# Nappe2_0___V2.net
KiCad netlist of a schematic drawn in EAGLE
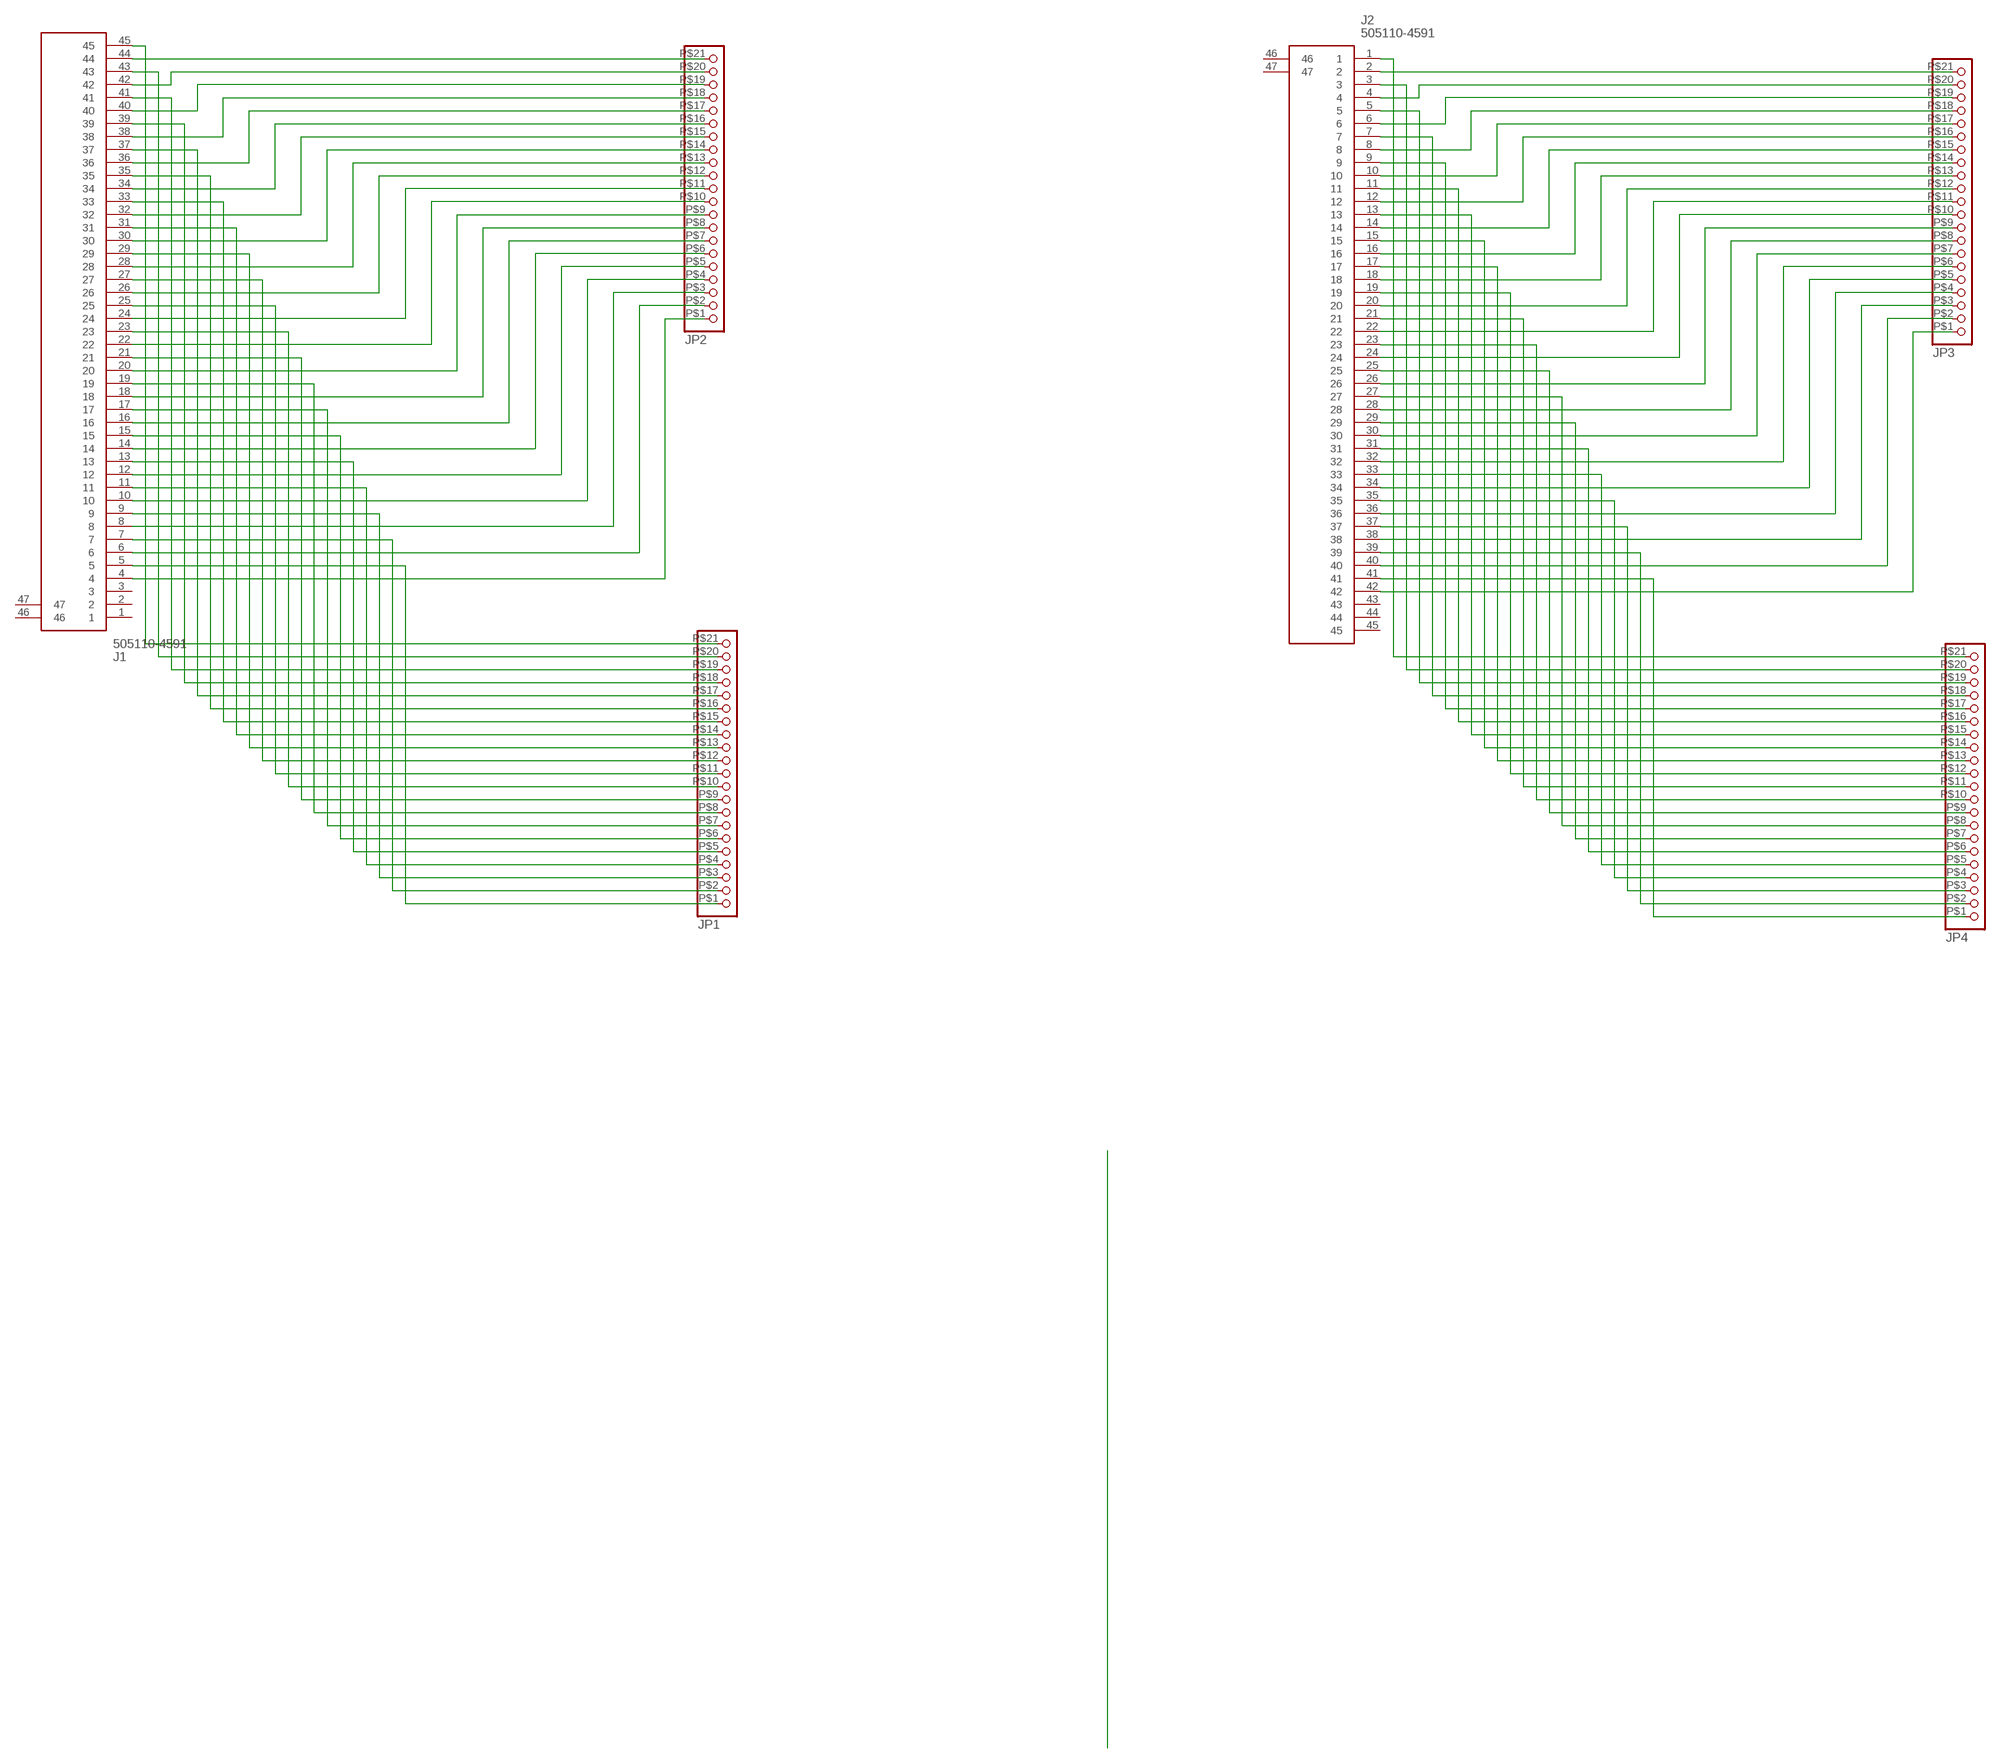
[diagram p0: schematic, sheet 1]

(export (version "E")
  (design (tool "Eeschema 10.0.6"))
  (components
    (comp (ref "J1")
      (value "505110-4591")
      (footprint "eagle-import:5051104591")
      (fields (field (name "MOUSER_PART_NUMBER") "538-505110-4591"))
      (libsource (lib "eagle-import") (part "505110-4591"))
    )
    (comp (ref "J2")
      (value "505110-4591")
      (footprint "eagle-import:5051104591")
      (fields (field (name "MOUSER_PART_NUMBER") "538-505110-4591"))
      (libsource (lib "eagle-import") (part "505110-4591"))
    )
    (comp (ref "JP1")
      (value "PINHD-1X21(2.5)")
      (footprint "eagle-import:1X21(2.5)")
      (libsource (lib "eagle-import") (part "PINHD-1X21(2.5)"))
    )
    (comp (ref "JP2")
      (value "PINHD-1X21(2.5)")
      (footprint "eagle-import:1X21(2.5)")
      (libsource (lib "eagle-import") (part "PINHD-1X21(2.5)"))
    )
    (comp (ref "JP3")
      (value "PINHD-1X21(2.5)")
      (footprint "eagle-import:1X21(2.5)")
      (libsource (lib "eagle-import") (part "PINHD-1X21(2.5)"))
    )
    (comp (ref "JP4")
      (value "PINHD-1X21(2.5)")
      (footprint "eagle-import:1X21(2.5)")
      (libsource (lib "eagle-import") (part "PINHD-1X21(2.5)"))
    )
  )
  (nets
    (net (code "1") (name "Net-(JP1-1)") (class "Default")
      (node (ref "J1") (pin "5") (pinfunction "5_5") (pintype "bidirectional"))
      (node (ref "JP1") (pin "P$1") (pinfunction "1_P$1") (pintype "passive"))
    )
    (net (code "2") (name "Net-(JP1-2)") (class "Default")
      (node (ref "J1") (pin "7") (pinfunction "7_7") (pintype "bidirectional"))
      (node (ref "JP1") (pin "P$2") (pinfunction "2_P$2") (pintype "passive"))
    )
    (net (code "3") (name "Net-(JP1-3)") (class "Default")
      (node (ref "J1") (pin "9") (pinfunction "9_9") (pintype "bidirectional"))
      (node (ref "JP1") (pin "P$3") (pinfunction "3_P$3") (pintype "passive"))
    )
    (net (code "4") (name "Net-(JP1-4)") (class "Default")
      (node (ref "J1") (pin "11") (pinfunction "11_11") (pintype "bidirectional"))
      (node (ref "JP1") (pin "P$4") (pinfunction "4_P$4") (pintype "passive"))
    )
    (net (code "5") (name "Net-(JP1-5)") (class "Default")
      (node (ref "J1") (pin "13") (pinfunction "13_13") (pintype "bidirectional"))
      (node (ref "JP1") (pin "P$5") (pinfunction "5_P$5") (pintype "passive"))
    )
    (net (code "6") (name "Net-(JP1-6)") (class "Default")
      (node (ref "J1") (pin "15") (pinfunction "15_15") (pintype "bidirectional"))
      (node (ref "JP1") (pin "P$6") (pinfunction "6_P$6") (pintype "passive"))
    )
    (net (code "7") (name "Net-(JP1-7)") (class "Default")
      (node (ref "J1") (pin "17") (pinfunction "17_17") (pintype "bidirectional"))
      (node (ref "JP1") (pin "P$7") (pinfunction "7_P$7") (pintype "passive"))
    )
    (net (code "8") (name "Net-(JP1-8)") (class "Default")
      (node (ref "J1") (pin "19") (pinfunction "19_19") (pintype "bidirectional"))
      (node (ref "JP1") (pin "P$8") (pinfunction "8_P$8") (pintype "passive"))
    )
    (net (code "9") (name "Net-(JP1-9)") (class "Default")
      (node (ref "J1") (pin "21") (pinfunction "21_21") (pintype "bidirectional"))
      (node (ref "JP1") (pin "P$9") (pinfunction "9_P$9") (pintype "passive"))
    )
    (net (code "10") (name "Net-(JP1-10)") (class "Default")
      (node (ref "J1") (pin "23") (pinfunction "23_23") (pintype "bidirectional"))
      (node (ref "JP1") (pin "P$10") (pinfunction "10_P$10") (pintype "passive"))
    )
    (net (code "11") (name "Net-(JP1-11)") (class "Default")
      (node (ref "J1") (pin "25") (pinfunction "25_25") (pintype "bidirectional"))
      (node (ref "JP1") (pin "P$11") (pinfunction "11_P$11") (pintype "passive"))
    )
    (net (code "12") (name "Net-(JP1-12)") (class "Default")
      (node (ref "J1") (pin "27") (pinfunction "27_27") (pintype "bidirectional"))
      (node (ref "JP1") (pin "P$12") (pinfunction "12_P$12") (pintype "passive"))
    )
    (net (code "13") (name "Net-(JP1-13)") (class "Default")
      (node (ref "J1") (pin "29") (pinfunction "29_29") (pintype "bidirectional"))
      (node (ref "JP1") (pin "P$13") (pinfunction "13_P$13") (pintype "passive"))
    )
    (net (code "14") (name "Net-(JP1-14)") (class "Default")
      (node (ref "J1") (pin "31") (pinfunction "31_31") (pintype "bidirectional"))
      (node (ref "JP1") (pin "P$14") (pinfunction "14_P$14") (pintype "passive"))
    )
    (net (code "15") (name "Net-(JP1-15)") (class "Default")
      (node (ref "J1") (pin "33") (pinfunction "33_33") (pintype "bidirectional"))
      (node (ref "JP1") (pin "P$15") (pinfunction "15_P$15") (pintype "passive"))
    )
    (net (code "16") (name "Net-(JP1-16)") (class "Default")
      (node (ref "J1") (pin "35") (pinfunction "35_35") (pintype "bidirectional"))
      (node (ref "JP1") (pin "P$16") (pinfunction "16_P$16") (pintype "passive"))
    )
    (net (code "17") (name "Net-(JP1-17)") (class "Default")
      (node (ref "J1") (pin "37") (pinfunction "37_37") (pintype "bidirectional"))
      (node (ref "JP1") (pin "P$17") (pinfunction "17_P$17") (pintype "passive"))
    )
    (net (code "18") (name "Net-(JP1-18)") (class "Default")
      (node (ref "J1") (pin "39") (pinfunction "39_39") (pintype "bidirectional"))
      (node (ref "JP1") (pin "P$18") (pinfunction "18_P$18") (pintype "passive"))
    )
    (net (code "19") (name "Net-(JP1-19)") (class "Default")
      (node (ref "J1") (pin "41") (pinfunction "41_41") (pintype "bidirectional"))
      (node (ref "JP1") (pin "P$19") (pinfunction "19_P$19") (pintype "passive"))
    )
    (net (code "20") (name "Net-(JP1-20)") (class "Default")
      (node (ref "J1") (pin "43") (pinfunction "43_43") (pintype "bidirectional"))
      (node (ref "JP1") (pin "P$20") (pinfunction "20_P$20") (pintype "passive"))
    )
    (net (code "21") (name "Net-(JP1-21)") (class "Default")
      (node (ref "J1") (pin "45") (pinfunction "45_45") (pintype "bidirectional"))
      (node (ref "JP1") (pin "P$21") (pinfunction "21_P$21") (pintype "passive"))
    )
    (net (code "22") (name "Net-(JP2-1)") (class "Default")
      (node (ref "J1") (pin "4") (pinfunction "4_4") (pintype "bidirectional"))
      (node (ref "JP2") (pin "P$1") (pinfunction "1_P$1") (pintype "passive"))
    )
    (net (code "23") (name "Net-(JP2-2)") (class "Default")
      (node (ref "J1") (pin "6") (pinfunction "6_6") (pintype "bidirectional"))
      (node (ref "JP2") (pin "P$2") (pinfunction "2_P$2") (pintype "passive"))
    )
    (net (code "24") (name "Net-(JP2-3)") (class "Default")
      (node (ref "J1") (pin "8") (pinfunction "8_8") (pintype "bidirectional"))
      (node (ref "JP2") (pin "P$3") (pinfunction "3_P$3") (pintype "passive"))
    )
    (net (code "25") (name "Net-(JP2-4)") (class "Default")
      (node (ref "J1") (pin "10") (pinfunction "10_10") (pintype "bidirectional"))
      (node (ref "JP2") (pin "P$4") (pinfunction "4_P$4") (pintype "passive"))
    )
    (net (code "26") (name "Net-(JP2-5)") (class "Default")
      (node (ref "J1") (pin "12") (pinfunction "12_12") (pintype "bidirectional"))
      (node (ref "JP2") (pin "P$5") (pinfunction "5_P$5") (pintype "passive"))
    )
    (net (code "27") (name "Net-(JP2-6)") (class "Default")
      (node (ref "J1") (pin "14") (pinfunction "14_14") (pintype "bidirectional"))
      (node (ref "JP2") (pin "P$6") (pinfunction "6_P$6") (pintype "passive"))
    )
    (net (code "28") (name "Net-(JP2-7)") (class "Default")
      (node (ref "J1") (pin "16") (pinfunction "16_16") (pintype "bidirectional"))
      (node (ref "JP2") (pin "P$7") (pinfunction "7_P$7") (pintype "passive"))
    )
    (net (code "29") (name "Net-(JP2-8)") (class "Default")
      (node (ref "J1") (pin "18") (pinfunction "18_18") (pintype "bidirectional"))
      (node (ref "JP2") (pin "P$8") (pinfunction "8_P$8") (pintype "passive"))
    )
    (net (code "30") (name "Net-(JP2-9)") (class "Default")
      (node (ref "J1") (pin "20") (pinfunction "20_20") (pintype "bidirectional"))
      (node (ref "JP2") (pin "P$9") (pinfunction "9_P$9") (pintype "passive"))
    )
    (net (code "31") (name "Net-(JP2-10)") (class "Default")
      (node (ref "J1") (pin "22") (pinfunction "22_22") (pintype "bidirectional"))
      (node (ref "JP2") (pin "P$10") (pinfunction "10_P$10") (pintype "passive"))
    )
    (net (code "32") (name "Net-(JP2-11)") (class "Default")
      (node (ref "J1") (pin "24") (pinfunction "24_24") (pintype "bidirectional"))
      (node (ref "JP2") (pin "P$11") (pinfunction "11_P$11") (pintype "passive"))
    )
    (net (code "33") (name "Net-(JP2-12)") (class "Default")
      (node (ref "J1") (pin "26") (pinfunction "26_26") (pintype "bidirectional"))
      (node (ref "JP2") (pin "P$12") (pinfunction "12_P$12") (pintype "passive"))
    )
    (net (code "34") (name "Net-(JP2-13)") (class "Default")
      (node (ref "J1") (pin "28") (pinfunction "28_28") (pintype "bidirectional"))
      (node (ref "JP2") (pin "P$13") (pinfunction "13_P$13") (pintype "passive"))
    )
    (net (code "35") (name "Net-(JP2-14)") (class "Default")
      (node (ref "J1") (pin "30") (pinfunction "30_30") (pintype "bidirectional"))
      (node (ref "JP2") (pin "P$14") (pinfunction "14_P$14") (pintype "passive"))
    )
    (net (code "36") (name "Net-(JP2-15)") (class "Default")
      (node (ref "J1") (pin "32") (pinfunction "32_32") (pintype "bidirectional"))
      (node (ref "JP2") (pin "P$15") (pinfunction "15_P$15") (pintype "passive"))
    )
    (net (code "37") (name "Net-(JP2-16)") (class "Default")
      (node (ref "J1") (pin "34") (pinfunction "34_34") (pintype "bidirectional"))
      (node (ref "JP2") (pin "P$16") (pinfunction "16_P$16") (pintype "passive"))
    )
    (net (code "38") (name "Net-(JP2-17)") (class "Default")
      (node (ref "J1") (pin "36") (pinfunction "36_36") (pintype "bidirectional"))
      (node (ref "JP2") (pin "P$17") (pinfunction "17_P$17") (pintype "passive"))
    )
    (net (code "39") (name "Net-(JP2-18)") (class "Default")
      (node (ref "J1") (pin "38") (pinfunction "38_38") (pintype "bidirectional"))
      (node (ref "JP2") (pin "P$18") (pinfunction "18_P$18") (pintype "passive"))
    )
    (net (code "40") (name "Net-(JP2-19)") (class "Default")
      (node (ref "J1") (pin "40") (pinfunction "40_40") (pintype "bidirectional"))
      (node (ref "JP2") (pin "P$19") (pinfunction "19_P$19") (pintype "passive"))
    )
    (net (code "41") (name "Net-(JP2-20)") (class "Default")
      (node (ref "J1") (pin "42") (pinfunction "42_42") (pintype "bidirectional"))
      (node (ref "JP2") (pin "P$20") (pinfunction "20_P$20") (pintype "passive"))
    )
    (net (code "42") (name "Net-(JP2-21)") (class "Default")
      (node (ref "J1") (pin "44") (pinfunction "44_44") (pintype "bidirectional"))
      (node (ref "JP2") (pin "P$21") (pinfunction "21_P$21") (pintype "passive"))
    )
    (net (code "43") (name "Net-(JP3-1)") (class "Default")
      (node (ref "J2") (pin "42") (pinfunction "42_42") (pintype "bidirectional"))
      (node (ref "JP3") (pin "P$1") (pinfunction "1_P$1") (pintype "passive"))
    )
    (net (code "44") (name "Net-(JP3-2)") (class "Default")
      (node (ref "J2") (pin "40") (pinfunction "40_40") (pintype "bidirectional"))
      (node (ref "JP3") (pin "P$2") (pinfunction "2_P$2") (pintype "passive"))
    )
    (net (code "45") (name "Net-(JP3-3)") (class "Default")
      (node (ref "J2") (pin "38") (pinfunction "38_38") (pintype "bidirectional"))
      (node (ref "JP3") (pin "P$3") (pinfunction "3_P$3") (pintype "passive"))
    )
    (net (code "46") (name "Net-(JP3-4)") (class "Default")
      (node (ref "J2") (pin "36") (pinfunction "36_36") (pintype "bidirectional"))
      (node (ref "JP3") (pin "P$4") (pinfunction "4_P$4") (pintype "passive"))
    )
    (net (code "47") (name "Net-(JP3-5)") (class "Default")
      (node (ref "J2") (pin "34") (pinfunction "34_34") (pintype "bidirectional"))
      (node (ref "JP3") (pin "P$5") (pinfunction "5_P$5") (pintype "passive"))
    )
    (net (code "48") (name "Net-(JP3-6)") (class "Default")
      (node (ref "J2") (pin "32") (pinfunction "32_32") (pintype "bidirectional"))
      (node (ref "JP3") (pin "P$6") (pinfunction "6_P$6") (pintype "passive"))
    )
    (net (code "49") (name "Net-(JP3-7)") (class "Default")
      (node (ref "J2") (pin "30") (pinfunction "30_30") (pintype "bidirectional"))
      (node (ref "JP3") (pin "P$7") (pinfunction "7_P$7") (pintype "passive"))
    )
    (net (code "50") (name "Net-(JP3-8)") (class "Default")
      (node (ref "J2") (pin "28") (pinfunction "28_28") (pintype "bidirectional"))
      (node (ref "JP3") (pin "P$8") (pinfunction "8_P$8") (pintype "passive"))
    )
    (net (code "51") (name "Net-(JP3-9)") (class "Default")
      (node (ref "J2") (pin "26") (pinfunction "26_26") (pintype "bidirectional"))
      (node (ref "JP3") (pin "P$9") (pinfunction "9_P$9") (pintype "passive"))
    )
    (net (code "52") (name "Net-(JP3-10)") (class "Default")
      (node (ref "J2") (pin "24") (pinfunction "24_24") (pintype "bidirectional"))
      (node (ref "JP3") (pin "P$10") (pinfunction "10_P$10") (pintype "passive"))
    )
    (net (code "53") (name "Net-(JP3-11)") (class "Default")
      (node (ref "J2") (pin "22") (pinfunction "22_22") (pintype "bidirectional"))
      (node (ref "JP3") (pin "P$11") (pinfunction "11_P$11") (pintype "passive"))
    )
    (net (code "54") (name "Net-(JP3-12)") (class "Default")
      (node (ref "J2") (pin "20") (pinfunction "20_20") (pintype "bidirectional"))
      (node (ref "JP3") (pin "P$12") (pinfunction "12_P$12") (pintype "passive"))
    )
    (net (code "55") (name "Net-(JP3-13)") (class "Default")
      (node (ref "J2") (pin "18") (pinfunction "18_18") (pintype "bidirectional"))
      (node (ref "JP3") (pin "P$13") (pinfunction "13_P$13") (pintype "passive"))
    )
    (net (code "56") (name "Net-(JP3-14)") (class "Default")
      (node (ref "J2") (pin "16") (pinfunction "16_16") (pintype "bidirectional"))
      (node (ref "JP3") (pin "P$14") (pinfunction "14_P$14") (pintype "passive"))
    )
    (net (code "57") (name "Net-(JP3-15)") (class "Default")
      (node (ref "J2") (pin "14") (pinfunction "14_14") (pintype "bidirectional"))
      (node (ref "JP3") (pin "P$15") (pinfunction "15_P$15") (pintype "passive"))
    )
    (net (code "58") (name "Net-(JP3-16)") (class "Default")
      (node (ref "J2") (pin "12") (pinfunction "12_12") (pintype "bidirectional"))
      (node (ref "JP3") (pin "P$16") (pinfunction "16_P$16") (pintype "passive"))
    )
    (net (code "59") (name "Net-(JP3-17)") (class "Default")
      (node (ref "J2") (pin "10") (pinfunction "10_10") (pintype "bidirectional"))
      (node (ref "JP3") (pin "P$17") (pinfunction "17_P$17") (pintype "passive"))
    )
    (net (code "60") (name "Net-(JP3-18)") (class "Default")
      (node (ref "J2") (pin "8") (pinfunction "8_8") (pintype "bidirectional"))
      (node (ref "JP3") (pin "P$18") (pinfunction "18_P$18") (pintype "passive"))
    )
    (net (code "61") (name "Net-(JP3-19)") (class "Default")
      (node (ref "J2") (pin "6") (pinfunction "6_6") (pintype "bidirectional"))
      (node (ref "JP3") (pin "P$19") (pinfunction "19_P$19") (pintype "passive"))
    )
    (net (code "62") (name "Net-(JP3-20)") (class "Default")
      (node (ref "J2") (pin "4") (pinfunction "4_4") (pintype "bidirectional"))
      (node (ref "JP3") (pin "P$20") (pinfunction "20_P$20") (pintype "passive"))
    )
    (net (code "63") (name "Net-(JP3-21)") (class "Default")
      (node (ref "J2") (pin "2") (pinfunction "2_2") (pintype "bidirectional"))
      (node (ref "JP3") (pin "P$21") (pinfunction "21_P$21") (pintype "passive"))
    )
    (net (code "64") (name "Net-(JP4-1)") (class "Default")
      (node (ref "J2") (pin "41") (pinfunction "41_41") (pintype "bidirectional"))
      (node (ref "JP4") (pin "P$1") (pinfunction "1_P$1") (pintype "passive"))
    )
    (net (code "65") (name "Net-(JP4-2)") (class "Default")
      (node (ref "J2") (pin "39") (pinfunction "39_39") (pintype "bidirectional"))
      (node (ref "JP4") (pin "P$2") (pinfunction "2_P$2") (pintype "passive"))
    )
    (net (code "66") (name "Net-(JP4-3)") (class "Default")
      (node (ref "J2") (pin "37") (pinfunction "37_37") (pintype "bidirectional"))
      (node (ref "JP4") (pin "P$3") (pinfunction "3_P$3") (pintype "passive"))
    )
    (net (code "67") (name "Net-(JP4-4)") (class "Default")
      (node (ref "J2") (pin "35") (pinfunction "35_35") (pintype "bidirectional"))
      (node (ref "JP4") (pin "P$4") (pinfunction "4_P$4") (pintype "passive"))
    )
    (net (code "68") (name "Net-(JP4-5)") (class "Default")
      (node (ref "J2") (pin "33") (pinfunction "33_33") (pintype "bidirectional"))
      (node (ref "JP4") (pin "P$5") (pinfunction "5_P$5") (pintype "passive"))
    )
    (net (code "69") (name "Net-(JP4-6)") (class "Default")
      (node (ref "J2") (pin "31") (pinfunction "31_31") (pintype "bidirectional"))
      (node (ref "JP4") (pin "P$6") (pinfunction "6_P$6") (pintype "passive"))
    )
    (net (code "70") (name "Net-(JP4-7)") (class "Default")
      (node (ref "J2") (pin "29") (pinfunction "29_29") (pintype "bidirectional"))
      (node (ref "JP4") (pin "P$7") (pinfunction "7_P$7") (pintype "passive"))
    )
    (net (code "71") (name "Net-(JP4-8)") (class "Default")
      (node (ref "J2") (pin "27") (pinfunction "27_27") (pintype "bidirectional"))
      (node (ref "JP4") (pin "P$8") (pinfunction "8_P$8") (pintype "passive"))
    )
    (net (code "72") (name "Net-(JP4-9)") (class "Default")
      (node (ref "J2") (pin "25") (pinfunction "25_25") (pintype "bidirectional"))
      (node (ref "JP4") (pin "P$9") (pinfunction "9_P$9") (pintype "passive"))
    )
    (net (code "73") (name "Net-(JP4-10)") (class "Default")
      (node (ref "J2") (pin "23") (pinfunction "23_23") (pintype "bidirectional"))
      (node (ref "JP4") (pin "P$10") (pinfunction "10_P$10") (pintype "passive"))
    )
    (net (code "74") (name "Net-(JP4-11)") (class "Default")
      (node (ref "J2") (pin "21") (pinfunction "21_21") (pintype "bidirectional"))
      (node (ref "JP4") (pin "P$11") (pinfunction "11_P$11") (pintype "passive"))
    )
    (net (code "75") (name "Net-(JP4-12)") (class "Default")
      (node (ref "J2") (pin "19") (pinfunction "19_19") (pintype "bidirectional"))
      (node (ref "JP4") (pin "P$12") (pinfunction "12_P$12") (pintype "passive"))
    )
    (net (code "76") (name "Net-(JP4-13)") (class "Default")
      (node (ref "J2") (pin "17") (pinfunction "17_17") (pintype "bidirectional"))
      (node (ref "JP4") (pin "P$13") (pinfunction "13_P$13") (pintype "passive"))
    )
    (net (code "77") (name "Net-(JP4-14)") (class "Default")
      (node (ref "J2") (pin "15") (pinfunction "15_15") (pintype "bidirectional"))
      (node (ref "JP4") (pin "P$14") (pinfunction "14_P$14") (pintype "passive"))
    )
    (net (code "78") (name "Net-(JP4-15)") (class "Default")
      (node (ref "J2") (pin "13") (pinfunction "13_13") (pintype "bidirectional"))
      (node (ref "JP4") (pin "P$15") (pinfunction "15_P$15") (pintype "passive"))
    )
    (net (code "79") (name "Net-(JP4-16)") (class "Default")
      (node (ref "J2") (pin "11") (pinfunction "11_11") (pintype "bidirectional"))
      (node (ref "JP4") (pin "P$16") (pinfunction "16_P$16") (pintype "passive"))
    )
    (net (code "80") (name "Net-(JP4-17)") (class "Default")
      (node (ref "J2") (pin "9") (pinfunction "9_9") (pintype "bidirectional"))
      (node (ref "JP4") (pin "P$17") (pinfunction "17_P$17") (pintype "passive"))
    )
    (net (code "81") (name "Net-(JP4-18)") (class "Default")
      (node (ref "J2") (pin "7") (pinfunction "7_7") (pintype "bidirectional"))
      (node (ref "JP4") (pin "P$18") (pinfunction "18_P$18") (pintype "passive"))
    )
    (net (code "82") (name "Net-(JP4-19)") (class "Default")
      (node (ref "J2") (pin "5") (pinfunction "5_5") (pintype "bidirectional"))
      (node (ref "JP4") (pin "P$19") (pinfunction "19_P$19") (pintype "passive"))
    )
    (net (code "83") (name "Net-(JP4-20)") (class "Default")
      (node (ref "J2") (pin "3") (pinfunction "3_3") (pintype "bidirectional"))
      (node (ref "JP4") (pin "P$20") (pinfunction "20_P$20") (pintype "passive"))
    )
    (net (code "84") (name "Net-(JP4-21)") (class "Default")
      (node (ref "J2") (pin "1") (pinfunction "1_1") (pintype "bidirectional"))
      (node (ref "JP4") (pin "P$21") (pinfunction "21_P$21") (pintype "passive"))
    )
    (net (code "85") (name "unconnected-(J1-Pad1)") (class "Default")
      (node (ref "J1") (pin "1") (pinfunction "1_1") (pintype "bidirectional"))
    )
    (net (code "86") (name "unconnected-(J1-Pad2)") (class "Default")
      (node (ref "J1") (pin "2") (pinfunction "2_2") (pintype "bidirectional"))
    )
    (net (code "87") (name "unconnected-(J1-Pad3)") (class "Default")
      (node (ref "J1") (pin "3") (pinfunction "3_3") (pintype "bidirectional"))
    )
    (net (code "88") (name "unconnected-(J1-Pad46)") (class "Default")
      (node (ref "J1") (pin "46") (pinfunction "46_46") (pintype "bidirectional"))
    )
    (net (code "89") (name "unconnected-(J1-Pad47)") (class "Default")
      (node (ref "J1") (pin "47") (pinfunction "47_47") (pintype "bidirectional"))
    )
    (net (code "90") (name "unconnected-(J2-Pad43)") (class "Default")
      (node (ref "J2") (pin "43") (pinfunction "43_43") (pintype "bidirectional"))
    )
    (net (code "91") (name "unconnected-(J2-Pad44)") (class "Default")
      (node (ref "J2") (pin "44") (pinfunction "44_44") (pintype "bidirectional"))
    )
    (net (code "92") (name "unconnected-(J2-Pad45)") (class "Default")
      (node (ref "J2") (pin "45") (pinfunction "45_45") (pintype "bidirectional"))
    )
    (net (code "93") (name "unconnected-(J2-Pad46)") (class "Default")
      (node (ref "J2") (pin "46") (pinfunction "46_46") (pintype "bidirectional"))
    )
    (net (code "94") (name "unconnected-(J2-Pad47)") (class "Default")
      (node (ref "J2") (pin "47") (pinfunction "47_47") (pintype "bidirectional"))
    )
  )
)
